# IO_Board.net
KiCad netlist of a schematic drawn in Altium Designer
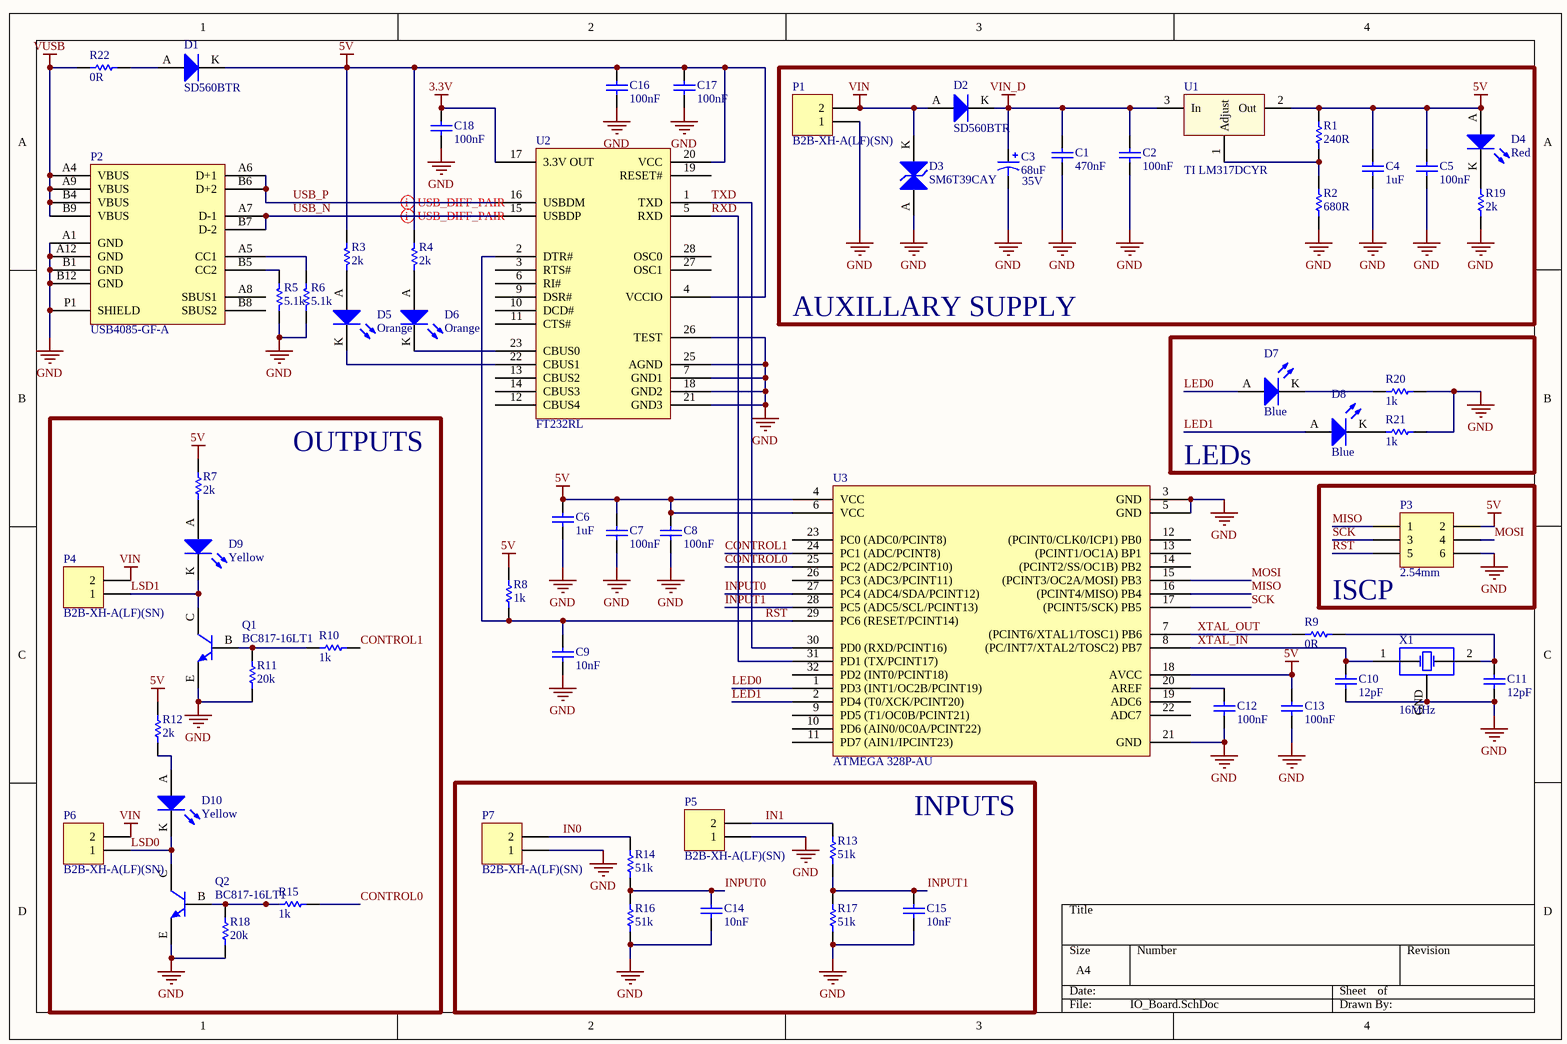
[diagram p0: IO_Board.SchDoc]

(export (version "E")
  (design (tool "Eeschema 10.0.6"))
  (components
    (comp (ref "C1")
      (value "470nF")
      (footprint "0805")
      (fields
        (field (name "PART NUMBER") "GCM21BR71H474KA37L")
        (field (name "TOLERANCE") "10%")
        (field (name "MANUFACTURER") "muRata")
      )
      (libsource (lib "ts_20-standard-library") (part "Capacitor"))
    )
    (comp (ref "C2")
      (value "100nF")
      (footprint "0805")
      (fields
        (field (name "PART NUMBER") "GCM21BR71E104KA37L")
        (field (name "TOLERANCE") "10%")
        (field (name "MANUFACTURER") "muRata")
      )
      (libsource (lib "ts_20-standard-library") (part "Capacitor"))
    )
    (comp (ref "C3")
      (value "68uF")
      (footprint "2924")
      (fields
        (field (name "PART NUMBER") "TAJV686K035RNJ")
        (field (name "TOLERANCE") "10%")
        (field (name "RATED VOLTAGE") "35V")
        (field (name "MANUFACTURER") "AVX Corporation")
      )
      (libsource (lib "ts_20-standard-library") (part "Capacitor (Polarised)"))
    )
    (comp (ref "C4")
      (value "1uF")
      (footprint "0805")
      (fields
        (field (name "PART NUMBER") "AC0805KKX7R8BB105")
        (field (name "TOLERANCE") "10%")
        (field (name "MANUFACTURER") "YAGEO")
      )
      (libsource (lib "ts_20-standard-library") (part "Capacitor"))
    )
    (comp (ref "C5")
      (value "100nF")
      (footprint "0805")
      (fields
        (field (name "PART NUMBER") "GCM21BR71E104KA37L")
        (field (name "TOLERANCE") "10%")
        (field (name "MANUFACTURER") "muRata")
      )
      (libsource (lib "ts_20-standard-library") (part "Capacitor"))
    )
    (comp (ref "C6")
      (value "1uF")
      (footprint "0805")
      (fields
        (field (name "PART NUMBER") "AC0805KKX7R8BB105")
        (field (name "TOLERANCE") "10%")
        (field (name "MANUFACTURER") "YAGEO")
      )
      (libsource (lib "ts_20-standard-library") (part "Capacitor"))
    )
    (comp (ref "C7")
      (value "100nF")
      (footprint "0805")
      (fields
        (field (name "PART NUMBER") "GCM21BR71E104KA37L")
        (field (name "TOLERANCE") "10%")
        (field (name "MANUFACTURER") "muRata")
      )
      (libsource (lib "ts_20-standard-library") (part "Capacitor"))
    )
    (comp (ref "C8")
      (value "100nF")
      (footprint "0805")
      (fields
        (field (name "PART NUMBER") "GCM21BR71E104KA37L")
        (field (name "TOLERANCE") "10%")
        (field (name "MANUFACTURER") "muRata")
      )
      (libsource (lib "ts_20-standard-library") (part "Capacitor"))
    )
    (comp (ref "C9")
      (value "10nF")
      (footprint "0805")
      (fields
        (field (name "PART NUMBER") "GCM2195C1H103JA16D")
        (field (name "TOLERANCE") "±5%")
        (field (name "MANUFACTURER") "muRata")
      )
      (libsource (lib "ts_20-standard-library") (part "Capacitor"))
    )
    (comp (ref "C10")
      (value "12pF")
      (footprint "0805")
      (fields
        (field (name "PART NUMBER") "GCM21B5c1H120JA37L")
        (field (name "TOLERANCE") "5%")
        (field (name "MANUFACTURER") "muRata")
      )
      (libsource (lib "ts_20-standard-library") (part "Capacitor"))
    )
    (comp (ref "C11")
      (value "12pF")
      (footprint "0805")
      (fields
        (field (name "PART NUMBER") "GCM21B5c1H120JA37L")
        (field (name "TOLERANCE") "5%")
        (field (name "MANUFACTURER") "muRata")
      )
      (libsource (lib "ts_20-standard-library") (part "Capacitor"))
    )
    (comp (ref "C12")
      (value "100nF")
      (footprint "0805")
      (fields
        (field (name "PART NUMBER") "GCM21BR71E104KA37L")
        (field (name "TOLERANCE") "10%")
        (field (name "MANUFACTURER") "muRata")
      )
      (libsource (lib "ts_20-standard-library") (part "Capacitor"))
    )
    (comp (ref "C13")
      (value "100nF")
      (footprint "0805")
      (fields
        (field (name "PART NUMBER") "GCM21BR71E104KA37L")
        (field (name "TOLERANCE") "10%")
        (field (name "MANUFACTURER") "muRata")
      )
      (libsource (lib "ts_20-standard-library") (part "Capacitor"))
    )
    (comp (ref "C14")
      (value "10nF")
      (footprint "0805")
      (fields
        (field (name "PART NUMBER") "GCM21BR71H103KA37L")
        (field (name "TOLERANCE") "10%")
        (field (name "MANUFACTURER") "muRata")
      )
      (libsource (lib "ts_20-standard-library") (part "Capacitor"))
    )
    (comp (ref "C15")
      (value "10nF")
      (footprint "0805")
      (fields
        (field (name "PART NUMBER") "GCM21BR71H103KA37L")
        (field (name "TOLERANCE") "10%")
        (field (name "MANUFACTURER") "muRata")
      )
      (libsource (lib "ts_20-standard-library") (part "Capacitor"))
    )
    (comp (ref "C16")
      (value "100nF")
      (footprint "0805")
      (fields
        (field (name "PART NUMBER") "GCM21BR71E104KA37L")
        (field (name "TOLERANCE") "10%")
        (field (name "MANUFACTURER") "muRata")
      )
      (libsource (lib "ts_20-standard-library") (part "Capacitor"))
    )
    (comp (ref "C17")
      (value "100nF")
      (footprint "0805")
      (fields
        (field (name "PART NUMBER") "GCM21BR71E104KA37L")
        (field (name "TOLERANCE") "10%")
        (field (name "MANUFACTURER") "muRata")
      )
      (libsource (lib "ts_20-standard-library") (part "Capacitor"))
    )
    (comp (ref "C18")
      (value "100nF")
      (footprint "0805")
      (fields
        (field (name "PART NUMBER") "GCM21BR71E104KA37L")
        (field (name "TOLERANCE") "10%")
        (field (name "MANUFACTURER") "muRata")
      )
      (libsource (lib "ts_20-standard-library") (part "Capacitor"))
    )
    (comp (ref "D1")
      (value "SD560BTR")
      (footprint "SMB Diode")
      (description "1.2V_F 600V 5A SMB")
      (fields
        (field (name "MANUFACTURER") "SMC Diode Solutions")
        (field (name "DIGIKEY PART NUMBER") "1655-1530-2-ND")
      )
      (libsource (lib "ts_20-standard-library") (part "Diode"))
    )
    (comp (ref "D2")
      (value "SD560BTR")
      (footprint "SMB Diode")
      (description "1.2V_F 600V 5A SMB")
      (fields
        (field (name "MANUFACTURER") "SMC Diode Solutions")
        (field (name "DIGIKEY PART NUMBER") "1655-1530-2-ND")
      )
      (libsource (lib "ts_20-standard-library") (part "Diode"))
    )
    (comp (ref "D3")
      (value "SM6T39CAY")
      (footprint "ST SMB Diode")
      (description "42.8V Clamp 93A (8/20µs) Ipp Tvs Diode Surface Mount SMB (DO-214AA)")
      (fields (field (name "MANUFACTURER") "ST"))
      (libsource (lib "ts_20-standard-library") (part "Bidirectional Zener Diode"))
    )
    (comp (ref "D4")
      (value "Red")
      (footprint "0805 LED")
      (description "Red LED Indication - Discrete 1.75V 0805 (2012 Metric)")
      (fields (field (name "PART NUMBER") "SML-210LTT86") (field (name "MANUFACTURER") "ROHM Semiconductor"))
      (libsource (lib "ts_20-standard-library") (part "LED"))
    )
    (comp (ref "D5")
      (value "Orange")
      (footprint "0805 LED")
      (description "Orange LED Indication - Discrete 1.75V 0805 (2012 Metric)")
      (fields (field (name "PART NUMBER") "SML-211DTT86") (field (name "MANUFACTURER") "ROHM Semiconductor"))
      (libsource (lib "ts_20-standard-library") (part "LED"))
    )
    (comp (ref "D6")
      (value "Orange")
      (footprint "0805 LED")
      (description "Orange LED Indication - Discrete 1.75V 0805 (2012 Metric)")
      (fields (field (name "PART NUMBER") "SML-211DTT86") (field (name "MANUFACTURER") "ROHM Semiconductor"))
      (libsource (lib "ts_20-standard-library") (part "LED"))
    )
    (comp (ref "D7")
      (value "Blue")
      (footprint "0805 LED")
      (description "LED BLUE CLEAR 2012 SMD")
      (fields
        (field (name "PART NUMBER") "SML-MN2BCTT86C")
        (field (name "MANUFACTURER") "ROHM Semiconductor")
      )
      (libsource (lib "ts_20-standard-library") (part "LED"))
    )
    (comp (ref "D8")
      (value "Blue")
      (footprint "0805 LED")
      (description "LED BLUE CLEAR 2012 SMD")
      (fields
        (field (name "PART NUMBER") "SML-MN2BCTT86C")
        (field (name "MANUFACTURER") "ROHM Semiconductor")
      )
      (libsource (lib "ts_20-standard-library") (part "LED"))
    )
    (comp (ref "D9")
      (value "Yellow")
      (footprint "0805 LED")
      (description "Yellow LED Indication - Discrete 1.75V 0805 (2012 Metric)")
      (fields (field (name "PART NUMBER") "SML-211YTT86") (field (name "MANUFACTURER") "ROHM Semiconductor"))
      (libsource (lib "ts_20-standard-library") (part "LED"))
    )
    (comp (ref "D10")
      (value "Yellow")
      (footprint "0805 LED")
      (description "Yellow LED Indication - Discrete 1.75V 0805 (2012 Metric)")
      (fields (field (name "PART NUMBER") "SML-211YTT86") (field (name "MANUFACTURER") "ROHM Semiconductor"))
      (libsource (lib "ts_20-standard-library") (part "LED"))
    )
    (comp (ref "P1")
      (value "B2B-XH-A(LF)(SN)")
      (footprint "XH 2 PIN VERT")
      (fields (field (name "DIGIKEY PART NUMBER") "455-2247-ND") (field (name "CONTACT") "Tin"))
      (libsource (lib "ts_20-standard-connectors") (part "Header 1x2"))
    )
    (comp (ref "P2")
      (value "USB4085-GF-A")
      (footprint "USB4085-GF-A")
      (description "USB - C (Type - C) USB 2.0 Receptacle Connector 16 Position Through Hole, Right Angle")
      (fields (field (name "DIGIKEY PART NUMBER") "2073-USB4085-GF-ACT-ND"))
      (libsource (lib "ts_20-standard-connectors") (part "USB4085-GF-A"))
    )
    (comp (ref "P3")
      (value "2.54mm")
      (footprint "TH 2.54mm Header 2x3")
      (fields (field (name "PART NUMBER") "TH 2.54mm Header 2x3") (field (name "CONTACT") "NA"))
      (libsource (lib "ts_20-standard-connectors") (part "Header 2x3"))
    )
    (comp (ref "P4")
      (value "B2B-XH-A(LF)(SN)")
      (footprint "XH 2 PIN VERT")
      (fields (field (name "DIGIKEY PART NUMBER") "455-2247-ND") (field (name "CONTACT") "Tin"))
      (libsource (lib "ts_20-standard-connectors") (part "Header 1x2"))
    )
    (comp (ref "P5")
      (value "B2B-XH-A(LF)(SN)")
      (footprint "XH 2 PIN VERT")
      (fields (field (name "DIGIKEY PART NUMBER") "455-2247-ND") (field (name "CONTACT") "Tin"))
      (libsource (lib "ts_20-standard-connectors") (part "Header 1x2"))
    )
    (comp (ref "P6")
      (value "B2B-XH-A(LF)(SN)")
      (footprint "XH 2 PIN VERT")
      (fields (field (name "DIGIKEY PART NUMBER") "455-2247-ND") (field (name "CONTACT") "Tin"))
      (libsource (lib "ts_20-standard-connectors") (part "Header 1x2"))
    )
    (comp (ref "P7")
      (value "B2B-XH-A(LF)(SN)")
      (footprint "XH 2 PIN VERT")
      (fields (field (name "DIGIKEY PART NUMBER") "455-2247-ND") (field (name "CONTACT") "Tin"))
      (libsource (lib "ts_20-standard-connectors") (part "Header 1x2"))
    )
    (comp (ref "Q1")
      (value "BC817-16LT1")
      (footprint "ON SOT-23 BJT")
      (description "300mW  BJT NPN Transistor")
      (fields
        (field (name "MANUFACTURER") "ON Semiconductor")
        (field (name "DIGIKEY PART NUMBER") "BC817-16LT1OSTR-ND")
      )
      (libsource (lib "ts_20-standard-library") (part "NPN"))
    )
    (comp (ref "Q2")
      (value "BC817-16LT1")
      (footprint "ON SOT-23 BJT")
      (description "300mW  BJT NPN Transistor")
      (fields
        (field (name "MANUFACTURER") "ON Semiconductor")
        (field (name "DIGIKEY PART NUMBER") "BC817-16LT1OSTR-ND")
      )
      (libsource (lib "ts_20-standard-library") (part "NPN"))
    )
    (comp (ref "R1")
      (value "240R")
      (footprint "0805")
      (fields
        (field (name "PART NUMBER") "RC0805FR07240RL")
        (field (name "MANUFACTURER") "YAGEO")
        (field (name "TOLERANCE") "0.01")
      )
      (libsource (lib "ts_20-standard-library") (part "Resistor"))
    )
    (comp (ref "R2")
      (value "680R")
      (footprint "0805")
      (fields
        (field (name "PART NUMBER") "RC0805FR07680RL")
        (field (name "MANUFACTURER") "YAGEO")
        (field (name "TOLERANCE") "0.01")
      )
      (libsource (lib "ts_20-standard-library") (part "Resistor"))
    )
    (comp (ref "R3")
      (value "2k")
      (footprint "0805")
      (fields
        (field (name "PART NUMBER") "RC0805FR072KL")
        (field (name "MANUFACTURER") "YAGEO")
        (field (name "TOLERANCE") "0.01")
      )
      (libsource (lib "ts_20-standard-library") (part "Resistor"))
    )
    (comp (ref "R4")
      (value "2k")
      (footprint "0805")
      (fields
        (field (name "PART NUMBER") "RC0805FR072KL")
        (field (name "MANUFACTURER") "YAGEO")
        (field (name "TOLERANCE") "0.01")
      )
      (libsource (lib "ts_20-standard-library") (part "Resistor"))
    )
    (comp (ref "R5")
      (value "5.1k")
      (footprint "0805")
      (fields
        (field (name "PART NUMBER") "RC0805FR075K1L")
        (field (name "MANUFACTURER") "YAGEO")
        (field (name "TOLERANCE") "0.01")
      )
      (libsource (lib "ts_20-standard-library") (part "Resistor"))
    )
    (comp (ref "R6")
      (value "5.1k")
      (footprint "0805")
      (fields
        (field (name "PART NUMBER") "RC0805FR075K1L")
        (field (name "MANUFACTURER") "YAGEO")
        (field (name "TOLERANCE") "0.01")
      )
      (libsource (lib "ts_20-standard-library") (part "Resistor"))
    )
    (comp (ref "R7")
      (value "2k")
      (footprint "0805")
      (fields
        (field (name "PART NUMBER") "RC0805FR072KL")
        (field (name "MANUFACTURER") "YAGEO")
        (field (name "TOLERANCE") "0.01")
      )
      (libsource (lib "ts_20-standard-library") (part "Resistor"))
    )
    (comp (ref "R8")
      (value "1k")
      (footprint "0805")
      (fields
        (field (name "PART NUMBER") "RC0805FR071KL")
        (field (name "MANUFACTURER") "YAGEO")
        (field (name "TOLERANCE") "0.01")
      )
      (libsource (lib "ts_20-standard-library") (part "Resistor"))
    )
    (comp (ref "R9")
      (value "0R")
      (footprint "0805")
      (fields
        (field (name "PART NUMBER") "RC0805FR070RL")
        (field (name "MANUFACTURER") "YAGEO")
        (field (name "TOLERANCE") "0.01")
      )
      (libsource (lib "ts_20-standard-library") (part "Resistor"))
    )
    (comp (ref "R10")
      (value "1k")
      (footprint "0805")
      (fields
        (field (name "PART NUMBER") "RC0805FR071KL")
        (field (name "MANUFACTURER") "YAGEO")
        (field (name "TOLERANCE") "0.01")
      )
      (libsource (lib "ts_20-standard-library") (part "Resistor"))
    )
    (comp (ref "R11")
      (value "20k")
      (footprint "0805")
      (fields
        (field (name "PART NUMBER") "RC0805FR0720KL")
        (field (name "MANUFACTURER") "YAGEO")
        (field (name "TOLERANCE") "0.01")
      )
      (libsource (lib "ts_20-standard-library") (part "Resistor"))
    )
    (comp (ref "R12")
      (value "2k")
      (footprint "0805")
      (fields
        (field (name "PART NUMBER") "RC0805FR072KL")
        (field (name "MANUFACTURER") "YAGEO")
        (field (name "TOLERANCE") "0.01")
      )
      (libsource (lib "ts_20-standard-library") (part "Resistor"))
    )
    (comp (ref "R13")
      (value "51k")
      (footprint "0805")
      (fields
        (field (name "PART NUMBER") "RC0805FR0751KL")
        (field (name "MANUFACTURER") "YAGEO")
        (field (name "TOLERANCE") "0.01")
      )
      (libsource (lib "ts_20-standard-library") (part "Resistor"))
    )
    (comp (ref "R14")
      (value "51k")
      (footprint "0805")
      (fields
        (field (name "PART NUMBER") "RC0805FR0751KL")
        (field (name "MANUFACTURER") "YAGEO")
        (field (name "TOLERANCE") "0.01")
      )
      (libsource (lib "ts_20-standard-library") (part "Resistor"))
    )
    (comp (ref "R15")
      (value "1k")
      (footprint "0805")
      (fields
        (field (name "PART NUMBER") "RC0805FR071KL")
        (field (name "MANUFACTURER") "YAGEO")
        (field (name "TOLERANCE") "0.01")
      )
      (libsource (lib "ts_20-standard-library") (part "Resistor"))
    )
    (comp (ref "R16")
      (value "51k")
      (footprint "0805")
      (fields
        (field (name "PART NUMBER") "RC0805FR0751KL")
        (field (name "MANUFACTURER") "YAGEO")
        (field (name "TOLERANCE") "0.01")
      )
      (libsource (lib "ts_20-standard-library") (part "Resistor"))
    )
    (comp (ref "R17")
      (value "51k")
      (footprint "0805")
      (fields
        (field (name "PART NUMBER") "RC0805FR0751KL")
        (field (name "MANUFACTURER") "YAGEO")
        (field (name "TOLERANCE") "0.01")
      )
      (libsource (lib "ts_20-standard-library") (part "Resistor"))
    )
    (comp (ref "R18")
      (value "20k")
      (footprint "0805")
      (fields
        (field (name "PART NUMBER") "RC0805FR0720KL")
        (field (name "MANUFACTURER") "YAGEO")
        (field (name "TOLERANCE") "0.01")
      )
      (libsource (lib "ts_20-standard-library") (part "Resistor"))
    )
    (comp (ref "R19")
      (value "2k")
      (footprint "0805")
      (fields
        (field (name "PART NUMBER") "RC0805FR072KL")
        (field (name "MANUFACTURER") "YAGEO")
        (field (name "TOLERANCE") "0.01")
      )
      (libsource (lib "ts_20-standard-library") (part "Resistor"))
    )
    (comp (ref "R20")
      (value "1k")
      (footprint "0805")
      (fields
        (field (name "PART NUMBER") "RC0805FR071KL")
        (field (name "MANUFACTURER") "YAGEO")
        (field (name "TOLERANCE") "0.01")
      )
      (libsource (lib "ts_20-standard-library") (part "Resistor"))
    )
    (comp (ref "R21")
      (value "1k")
      (footprint "0805")
      (fields
        (field (name "PART NUMBER") "RC0805FR071KL")
        (field (name "MANUFACTURER") "YAGEO")
        (field (name "TOLERANCE") "0.01")
      )
      (libsource (lib "ts_20-standard-library") (part "Resistor"))
    )
    (comp (ref "R22")
      (value "0R")
      (footprint "0805")
      (fields
        (field (name "PART NUMBER") "RC0805FR070RL")
        (field (name "MANUFACTURER") "YAGEO")
        (field (name "TOLERANCE") "0.01")
      )
      (libsource (lib "ts_20-standard-library") (part "Resistor"))
    )
    (comp (ref "U1")
      (value "TI LM317DCYR")
      (footprint "TI SOT-223")
      (description "Linear Voltage Regulator IC 1 Output 1.5A SOT-223-4")
      (fields
        (field (name "MANUFACTURER") "Texas Instruments")
        (field (name "DIGIKEY PART NUMBER") "296-12602-1-ND")
      )
      (libsource (lib "ts_20-standard-library") (part "TI LM317"))
    )
    (comp (ref "U2")
      (value "FT232RL")
      (footprint "FTDI 28-SSOP")
      (description "USB Bridge, USB to UART USB 2.0 UART Interface 28-SSOP")
      (fields (field (name "MANUFACTURER") "FTDI") (field (name "DIGIKEY PART NUMBER") "768-1007-1-ND"))
      (libsource (lib "ts_20-standard-library") (part "FT232RL"))
    )
    (comp (ref "U3")
      (value "ATMEGA 328P-AU")
      (footprint "ATMEL TQFP-32")
      (description "AVR AVR® ATmega Microcontroller IC 8-Bit 20MHz 32KB (16K x 16) FLASH 32-TQFP (7x7)")
      (fields (field (name "MANUFACTURER") "ATMEL") (field (name "DIGIKEY PART NUMBER") "ATMEGA328P-AU-ND"))
      (libsource (lib "ts_20-standard-library") (part "ATMEGA 328P-AU"))
    )
    (comp (ref "X1")
      (value "16MHz")
      (footprint "Abracon 4-SMD 3.2x2.5")
      (fields
        (field (name "PART NUMBER") "ABM8AIG-16.000MHZ-12-2Z-T3")
        (field (name "MANUFACTURER") "Abracon LLC")
        (field (name "DIGIKEY PART NUMBER") "535-13386-1-ND")
      )
      (libsource (lib "ts_20-standard-library") (part "Crystal (Shielded)"))
    )
  )
  (nets
    (net (code "1") (name "/CONTROL0") (class "Default")
      (node (ref "R15") (pin "2") (pinfunction "2_2") (pintype "passive"))
      (node (ref "U3") (pin "25") (pinfunction "PC2_(ADC2/PCINT10)_25") (pintype "passive"))
    )
    (net (code "2") (name "/CONTROL1") (class "Default")
      (node (ref "R10") (pin "2") (pinfunction "2_2") (pintype "passive"))
      (node (ref "U3") (pin "24") (pinfunction "PC1_(ADC/PCINT8)_24") (pintype "passive"))
    )
    (net (code "3") (name "/IN0") (class "Default")
      (node (ref "P7") (pin "2") (pinfunction "2_2") (pintype "passive"))
      (node (ref "R14") (pin "1") (pinfunction "1_1") (pintype "passive"))
    )
    (net (code "4") (name "/IN1") (class "Default")
      (node (ref "P5") (pin "2") (pinfunction "2_2") (pintype "passive"))
      (node (ref "R13") (pin "1") (pinfunction "1_1") (pintype "passive"))
    )
    (net (code "5") (name "/INPUT0") (class "Default")
      (node (ref "C14") (pin "2") (pinfunction "2_2") (pintype "passive"))
      (node (ref "R14") (pin "2") (pinfunction "2_2") (pintype "passive"))
      (node (ref "R16") (pin "1") (pinfunction "1_1") (pintype "passive"))
      (node (ref "U3") (pin "27") (pinfunction "PC4_(ADC4/SDA/PCINT12)_27") (pintype "passive"))
    )
    (net (code "6") (name "/INPUT1") (class "Default")
      (node (ref "C15") (pin "2") (pinfunction "2_2") (pintype "passive"))
      (node (ref "R13") (pin "2") (pinfunction "2_2") (pintype "passive"))
      (node (ref "R17") (pin "1") (pinfunction "1_1") (pintype "passive"))
      (node (ref "U3") (pin "28") (pinfunction "PC5_(ADC5/SCL/PCINT13)_28") (pintype "passive"))
    )
    (net (code "7") (name "/LED0") (class "Default")
      (node (ref "D7") (pin "A") (pinfunction "A_A") (pintype "passive"))
      (node (ref "U3") (pin "1") (pinfunction "PD3_(INT1/OC2B/PCINT19)_1") (pintype "passive"))
    )
    (net (code "8") (name "/LED1") (class "Default")
      (node (ref "D8") (pin "A") (pinfunction "A_A") (pintype "passive"))
      (node (ref "U3") (pin "2") (pinfunction "PD4_(T0/XCK/PCINT20)_2") (pintype "passive"))
    )
    (net (code "9") (name "/LSD0") (class "Default")
      (node (ref "D10") (pin "K") (pinfunction "K_K") (pintype "passive"))
      (node (ref "P6") (pin "1") (pinfunction "1_1") (pintype "passive"))
      (node (ref "Q2") (pin "C") (pinfunction "C_C") (pintype "passive"))
    )
    (net (code "10") (name "/LSD1") (class "Default")
      (node (ref "D9") (pin "K") (pinfunction "K_K") (pintype "passive"))
      (node (ref "P4") (pin "1") (pinfunction "1_1") (pintype "passive"))
      (node (ref "Q1") (pin "C") (pinfunction "C_C") (pintype "passive"))
    )
    (net (code "11") (name "/MISO") (class "Default")
      (node (ref "P3") (pin "1") (pinfunction "1_1") (pintype "passive"))
      (node (ref "U3") (pin "16") (pinfunction "(PCINT4/MISO)_PB4_16") (pintype "passive"))
    )
    (net (code "12") (name "/MOSI") (class "Default")
      (node (ref "P3") (pin "4") (pinfunction "4_4") (pintype "passive"))
      (node (ref "U3") (pin "15") (pinfunction "(PCINT3/OC2A/MOSI)_PB3_15") (pintype "passive"))
    )
    (net (code "13") (name "/RST") (class "Default")
      (node (ref "C9") (pin "2") (pinfunction "2_2") (pintype "passive"))
      (node (ref "P3") (pin "5") (pinfunction "5_5") (pintype "passive"))
      (node (ref "R8") (pin "1") (pinfunction "1_1") (pintype "passive"))
      (node (ref "U2") (pin "2") (pinfunction "DTR#_2") (pintype "power_in"))
      (node (ref "U3") (pin "29") (pinfunction "PC6_(RESET/PCINT14)_29") (pintype "passive"))
    )
    (net (code "14") (name "/RXD") (class "Default")
      (node (ref "U2") (pin "5") (pinfunction "RXD_5") (pintype "power_in"))
      (node (ref "U3") (pin "31") (pinfunction "PD1_(TX/PCINT17)_31") (pintype "passive"))
    )
    (net (code "15") (name "/SCK") (class "Default")
      (node (ref "P3") (pin "3") (pinfunction "3_3") (pintype "passive"))
      (node (ref "U3") (pin "17") (pinfunction "(PCINT5/SCK)_PB5_17") (pintype "passive"))
    )
    (net (code "16") (name "/TXD") (class "Default")
      (node (ref "U2") (pin "1") (pinfunction "TXD_1") (pintype "power_in"))
      (node (ref "U3") (pin "30") (pinfunction "PD0_(RXD/PCINT16)_30") (pintype "passive"))
    )
    (net (code "17") (name "/USB_N") (class "Default")
      (node (ref "P2") (pin "A7") (pinfunction "D-1_A7") (pintype "passive"))
      (node (ref "P2") (pin "B7") (pinfunction "D-2_B7") (pintype "passive"))
      (node (ref "U2") (pin "15") (pinfunction "USBDP_15") (pintype "power_in"))
    )
    (net (code "18") (name "/USB_P") (class "Default")
      (node (ref "P2") (pin "A6") (pinfunction "D+1_A6") (pintype "passive"))
      (node (ref "P2") (pin "B6") (pinfunction "D+2_B6") (pintype "passive"))
      (node (ref "U2") (pin "16") (pinfunction "USBDM_16") (pintype "power_in"))
    )
    (net (code "19") (name "/XTAL_IN") (class "Default")
      (node (ref "C10") (pin "2") (pinfunction "2_2") (pintype "passive"))
      (node (ref "U3") (pin "8") (pinfunction "(PC/INT7/XTAL2/TOSC2)_PB7_8") (pintype "passive"))
      (node (ref "X1") (pin "1") (pinfunction "OSC1_1") (pintype "passive"))
    )
    (net (code "20") (name "/XTAL_OUT") (class "Default")
      (node (ref "R9") (pin "1") (pinfunction "1_1") (pintype "passive"))
      (node (ref "U3") (pin "7") (pinfunction "(PCINT6/XTAL1/TOSC1)_PB6_7") (pintype "passive"))
    )
    (net (code "21") (name "3.3V") (class "Default")
      (node (ref "C18") (pin "2") (pinfunction "2_2") (pintype "passive"))
      (node (ref "U2") (pin "17") (pinfunction "3.3V_OUT_17") (pintype "power_in"))
    )
    (net (code "22") (name "5V") (class "Default")
      (node (ref "C13") (pin "2") (pinfunction "2_2") (pintype "passive"))
      (node (ref "C16") (pin "2") (pinfunction "2_2") (pintype "passive"))
      (node (ref "C17") (pin "2") (pinfunction "2_2") (pintype "passive"))
      (node (ref "C4") (pin "2") (pinfunction "2_2") (pintype "passive"))
      (node (ref "C5") (pin "2") (pinfunction "2_2") (pintype "passive"))
      (node (ref "C6") (pin "2") (pinfunction "2_2") (pintype "passive"))
      (node (ref "C7") (pin "2") (pinfunction "2_2") (pintype "passive"))
      (node (ref "C8") (pin "2") (pinfunction "2_2") (pintype "passive"))
      (node (ref "D1") (pin "K") (pinfunction "K_K") (pintype "passive"))
      (node (ref "D4") (pin "A") (pinfunction "A_A") (pintype "passive"))
      (node (ref "P3") (pin "2") (pinfunction "2_2") (pintype "passive"))
      (node (ref "R1") (pin "2") (pinfunction "2_2") (pintype "passive"))
      (node (ref "R12") (pin "2") (pinfunction "2_2") (pintype "passive"))
      (node (ref "R3") (pin "2") (pinfunction "2_2") (pintype "passive"))
      (node (ref "R4") (pin "2") (pinfunction "2_2") (pintype "passive"))
      (node (ref "R7") (pin "2") (pinfunction "2_2") (pintype "passive"))
      (node (ref "R8") (pin "2") (pinfunction "2_2") (pintype "passive"))
      (node (ref "U1") (pin "2") (pinfunction "Out_2") (pintype "passive"))
      (node (ref "U2") (pin "20") (pinfunction "VCC_20") (pintype "power_in"))
      (node (ref "U2") (pin "4") (pinfunction "VCCIO_4") (pintype "power_in"))
      (node (ref "U3") (pin "18") (pinfunction "AVCC_18") (pintype "passive"))
      (node (ref "U3") (pin "4") (pinfunction "VCC_4") (pintype "passive"))
      (node (ref "U3") (pin "6") (pinfunction "VCC_6") (pintype "passive"))
    )
    (net (code "23") (name "GND") (class "Default")
      (node (ref "C1") (pin "1") (pinfunction "1_1") (pintype "passive"))
      (node (ref "C10") (pin "1") (pinfunction "1_1") (pintype "passive"))
      (node (ref "C11") (pin "1") (pinfunction "1_1") (pintype "passive"))
      (node (ref "C12") (pin "1") (pinfunction "1_1") (pintype "passive"))
      (node (ref "C13") (pin "1") (pinfunction "1_1") (pintype "passive"))
      (node (ref "C14") (pin "1") (pinfunction "1_1") (pintype "passive"))
      (node (ref "C15") (pin "1") (pinfunction "1_1") (pintype "passive"))
      (node (ref "C16") (pin "1") (pinfunction "1_1") (pintype "passive"))
      (node (ref "C17") (pin "1") (pinfunction "1_1") (pintype "passive"))
      (node (ref "C18") (pin "1") (pinfunction "1_1") (pintype "passive"))
      (node (ref "C2") (pin "1") (pinfunction "1_1") (pintype "passive"))
      (node (ref "C3") (pin "1") (pinfunction "1_1") (pintype "passive"))
      (node (ref "C4") (pin "1") (pinfunction "1_1") (pintype "passive"))
      (node (ref "C5") (pin "1") (pinfunction "1_1") (pintype "passive"))
      (node (ref "C6") (pin "1") (pinfunction "1_1") (pintype "passive"))
      (node (ref "C7") (pin "1") (pinfunction "1_1") (pintype "passive"))
      (node (ref "C8") (pin "1") (pinfunction "1_1") (pintype "passive"))
      (node (ref "C9") (pin "1") (pinfunction "1_1") (pintype "passive"))
      (node (ref "D3") (pin "A") (pinfunction "A_A") (pintype "passive"))
      (node (ref "P1") (pin "1") (pinfunction "1_1") (pintype "passive"))
      (node (ref "P2") (pin "A1") (pinfunction "GND_A1") (pintype "passive"))
      (node (ref "P2") (pin "A12") (pinfunction "GND_A12") (pintype "passive"))
      (node (ref "P2") (pin "B1") (pinfunction "GND_B1") (pintype "passive"))
      (node (ref "P2") (pin "B12") (pinfunction "GND_B12") (pintype "passive"))
      (node (ref "P2") (pin "P1") (pinfunction "SHIELD_P1") (pintype "passive"))
      (node (ref "P3") (pin "6") (pinfunction "6_6") (pintype "passive"))
      (node (ref "P5") (pin "1") (pinfunction "1_1") (pintype "passive"))
      (node (ref "P7") (pin "1") (pinfunction "1_1") (pintype "passive"))
      (node (ref "Q1") (pin "E") (pinfunction "E_E") (pintype "passive"))
      (node (ref "Q2") (pin "E") (pinfunction "E_E") (pintype "passive"))
      (node (ref "R11") (pin "1") (pinfunction "1_1") (pintype "passive"))
      (node (ref "R16") (pin "2") (pinfunction "2_2") (pintype "passive"))
      (node (ref "R17") (pin "2") (pinfunction "2_2") (pintype "passive"))
      (node (ref "R18") (pin "1") (pinfunction "1_1") (pintype "passive"))
      (node (ref "R19") (pin "1") (pinfunction "1_1") (pintype "passive"))
      (node (ref "R2") (pin "1") (pinfunction "1_1") (pintype "passive"))
      (node (ref "R20") (pin "1") (pinfunction "1_1") (pintype "passive"))
      (node (ref "R21") (pin "1") (pinfunction "1_1") (pintype "passive"))
      (node (ref "R5") (pin "1") (pinfunction "1_1") (pintype "passive"))
      (node (ref "R6") (pin "1") (pinfunction "1_1") (pintype "passive"))
      (node (ref "U2") (pin "18") (pinfunction "GND2_18") (pintype "power_in"))
      (node (ref "U2") (pin "21") (pinfunction "GND3_21") (pintype "power_in"))
      (node (ref "U2") (pin "25") (pinfunction "AGND_25") (pintype "power_in"))
      (node (ref "U2") (pin "26") (pinfunction "TEST_26") (pintype "power_in"))
      (node (ref "U2") (pin "7") (pinfunction "GND1_7") (pintype "power_in"))
      (node (ref "U3") (pin "21") (pinfunction "GND_21") (pintype "passive"))
      (node (ref "U3") (pin "3") (pinfunction "GND_3") (pintype "passive"))
      (node (ref "U3") (pin "5") (pinfunction "GND_5") (pintype "passive"))
      (node (ref "X1") (pin "GND") (pinfunction "GND_GND") (pintype "passive"))
    )
    (net (code "24") (name "Net-(D1-PadA)") (class "Default")
      (node (ref "D1") (pin "A") (pinfunction "A_A") (pintype "passive"))
      (node (ref "R22") (pin "2") (pinfunction "2_2") (pintype "passive"))
    )
    (net (code "25") (name "Net-(D4-PadK)") (class "Default")
      (node (ref "D4") (pin "K") (pinfunction "K_K") (pintype "passive"))
      (node (ref "R19") (pin "2") (pinfunction "2_2") (pintype "passive"))
    )
    (net (code "26") (name "Net-(D5-PadA)") (class "Default")
      (node (ref "D5") (pin "A") (pinfunction "A_A") (pintype "passive"))
      (node (ref "R3") (pin "1") (pinfunction "1_1") (pintype "passive"))
    )
    (net (code "27") (name "Net-(D6-PadA)") (class "Default")
      (node (ref "D6") (pin "A") (pinfunction "A_A") (pintype "passive"))
      (node (ref "R4") (pin "1") (pinfunction "1_1") (pintype "passive"))
    )
    (net (code "28") (name "Net-(D7-PadK)") (class "Default")
      (node (ref "D7") (pin "K") (pinfunction "K_K") (pintype "passive"))
      (node (ref "R20") (pin "2") (pinfunction "2_2") (pintype "passive"))
    )
    (net (code "29") (name "Net-(D8-PadK)") (class "Default")
      (node (ref "D8") (pin "K") (pinfunction "K_K") (pintype "passive"))
      (node (ref "R21") (pin "2") (pinfunction "2_2") (pintype "passive"))
    )
    (net (code "30") (name "Net-(D9-PadA)") (class "Default")
      (node (ref "D9") (pin "A") (pinfunction "A_A") (pintype "passive"))
      (node (ref "R7") (pin "1") (pinfunction "1_1") (pintype "passive"))
    )
    (net (code "31") (name "Net-(D10-PadA)") (class "Default")
      (node (ref "D10") (pin "A") (pinfunction "A_A") (pintype "passive"))
      (node (ref "R12") (pin "1") (pinfunction "1_1") (pintype "passive"))
    )
    (net (code "32") (name "Net-(P2-CC1)") (class "Default")
      (node (ref "P2") (pin "A5") (pinfunction "CC1_A5") (pintype "passive"))
      (node (ref "R6") (pin "2") (pinfunction "2_2") (pintype "passive"))
    )
    (net (code "33") (name "Net-(P2-CC2)") (class "Default")
      (node (ref "P2") (pin "B5") (pinfunction "CC2_B5") (pintype "passive"))
      (node (ref "R5") (pin "2") (pinfunction "2_2") (pintype "passive"))
    )
    (net (code "34") (name "Net-(Q1-PadB)") (class "Default")
      (node (ref "Q1") (pin "B") (pinfunction "B_B") (pintype "passive"))
      (node (ref "R10") (pin "1") (pinfunction "1_1") (pintype "passive"))
      (node (ref "R11") (pin "2") (pinfunction "2_2") (pintype "passive"))
    )
    (net (code "35") (name "Net-(Q2-PadB)") (class "Default")
      (node (ref "Q2") (pin "B") (pinfunction "B_B") (pintype "passive"))
      (node (ref "R15") (pin "1") (pinfunction "1_1") (pintype "passive"))
      (node (ref "R18") (pin "2") (pinfunction "2_2") (pintype "passive"))
    )
    (net (code "36") (name "Net-(U1-Adjust)") (class "Default")
      (node (ref "R1") (pin "1") (pinfunction "1_1") (pintype "passive"))
      (node (ref "R2") (pin "2") (pinfunction "2_2") (pintype "passive"))
      (node (ref "U1") (pin "1") (pinfunction "Adjust_1") (pintype "passive"))
    )
    (net (code "37") (name "Net-(U2-CBUS0)") (class "Default")
      (node (ref "D6") (pin "K") (pinfunction "K_K") (pintype "passive"))
      (node (ref "U2") (pin "23") (pinfunction "CBUS0_23") (pintype "power_in"))
    )
    (net (code "38") (name "Net-(U2-CBUS1)") (class "Default")
      (node (ref "D5") (pin "K") (pinfunction "K_K") (pintype "passive"))
      (node (ref "U2") (pin "22") (pinfunction "CBUS1_22") (pintype "power_in"))
    )
    (net (code "39") (name "Net-(U3-AREF)") (class "Default")
      (node (ref "C12") (pin "2") (pinfunction "2_2") (pintype "passive"))
      (node (ref "U3") (pin "20") (pinfunction "AREF_20") (pintype "passive"))
    )
    (net (code "40") (name "Net-(X1-OSC2)") (class "Default")
      (node (ref "C11") (pin "2") (pinfunction "2_2") (pintype "passive"))
      (node (ref "R9") (pin "2") (pinfunction "2_2") (pintype "passive"))
      (node (ref "X1") (pin "2") (pinfunction "OSC2_2") (pintype "passive"))
    )
    (net (code "41") (name "VIN") (class "Default")
      (node (ref "D2") (pin "A") (pinfunction "A_A") (pintype "passive"))
      (node (ref "D3") (pin "K") (pinfunction "K_K") (pintype "passive"))
      (node (ref "P1") (pin "2") (pinfunction "2_2") (pintype "passive"))
      (node (ref "P4") (pin "2") (pinfunction "2_2") (pintype "passive"))
      (node (ref "P6") (pin "2") (pinfunction "2_2") (pintype "passive"))
    )
    (net (code "42") (name "VIN_D") (class "Default")
      (node (ref "C1") (pin "2") (pinfunction "2_2") (pintype "passive"))
      (node (ref "C2") (pin "2") (pinfunction "2_2") (pintype "passive"))
      (node (ref "C3") (pin "2") (pinfunction "2_2") (pintype "passive"))
      (node (ref "D2") (pin "K") (pinfunction "K_K") (pintype "passive"))
      (node (ref "U1") (pin "3") (pinfunction "In_3") (pintype "passive"))
    )
    (net (code "43") (name "VUSB") (class "Default")
      (node (ref "P2") (pin "A4") (pinfunction "VBUS_A4") (pintype "passive"))
      (node (ref "P2") (pin "A9") (pinfunction "VBUS_A9") (pintype "passive"))
      (node (ref "P2") (pin "B4") (pinfunction "VBUS_B4") (pintype "passive"))
      (node (ref "P2") (pin "B9") (pinfunction "VBUS_B9") (pintype "passive"))
      (node (ref "R22") (pin "1") (pinfunction "1_1") (pintype "passive"))
    )
    (net (code "44") (name "unconnected-(P2-SBUS1-PadA8)") (class "Default")
      (node (ref "P2") (pin "A8") (pinfunction "SBUS1_A8") (pintype "passive"))
    )
    (net (code "45") (name "unconnected-(P2-SBUS2-PadB8)") (class "Default")
      (node (ref "P2") (pin "B8") (pinfunction "SBUS2_B8") (pintype "passive"))
    )
    (net (code "46") (name "unconnected-(U2-CBUS2-Pad13)") (class "Default")
      (node (ref "U2") (pin "13") (pinfunction "CBUS2_13") (pintype "power_in"))
    )
    (net (code "47") (name "unconnected-(U2-CBUS3-Pad14)") (class "Default")
      (node (ref "U2") (pin "14") (pinfunction "CBUS3_14") (pintype "power_in"))
    )
    (net (code "48") (name "unconnected-(U2-CBUS4-Pad12)") (class "Default")
      (node (ref "U2") (pin "12") (pinfunction "CBUS4_12") (pintype "power_in"))
    )
    (net (code "49") (name "unconnected-(U2-CTS#-Pad11)") (class "Default")
      (node (ref "U2") (pin "11") (pinfunction "CTS#_11") (pintype "power_in"))
    )
    (net (code "50") (name "unconnected-(U2-DCD#-Pad10)") (class "Default")
      (node (ref "U2") (pin "10") (pinfunction "DCD#_10") (pintype "power_in"))
    )
    (net (code "51") (name "unconnected-(U2-DSR#-Pad9)") (class "Default")
      (node (ref "U2") (pin "9") (pinfunction "DSR#_9") (pintype "power_in"))
    )
    (net (code "52") (name "unconnected-(U2-OSC0-Pad28)") (class "Default")
      (node (ref "U2") (pin "28") (pinfunction "OSC0_28") (pintype "power_in"))
    )
    (net (code "53") (name "unconnected-(U2-OSC1-Pad27)") (class "Default")
      (node (ref "U2") (pin "27") (pinfunction "OSC1_27") (pintype "power_in"))
    )
    (net (code "54") (name "unconnected-(U2-RESET#-Pad19)") (class "Default")
      (node (ref "U2") (pin "19") (pinfunction "RESET#_19") (pintype "power_in"))
    )
    (net (code "55") (name "unconnected-(U2-RI#-Pad6)") (class "Default")
      (node (ref "U2") (pin "6") (pinfunction "RI#_6") (pintype "power_in"))
    )
    (net (code "56") (name "unconnected-(U2-RTS#-Pad3)") (class "Default")
      (node (ref "U2") (pin "3") (pinfunction "RTS#_3") (pintype "power_in"))
    )
    (net (code "57") (name "unconnected-(U3-(PCINT0{slash}CLK0{slash}ICP1)_PB0-Pad12)") (class "Default")
      (node (ref "U3") (pin "12") (pinfunction "(PCINT0/CLK0/ICP1)_PB0_12") (pintype "passive"))
    )
    (net (code "58") (name "unconnected-(U3-(PCINT1{slash}OC1A)_BP1-Pad13)") (class "Default")
      (node (ref "U3") (pin "13") (pinfunction "(PCINT1/OC1A)_BP1_13") (pintype "passive"))
    )
    (net (code "59") (name "unconnected-(U3-(PCINT2{slash}SS{slash}OC1B)_PB2-Pad14)") (class "Default")
      (node (ref "U3") (pin "14") (pinfunction "(PCINT2/SS/OC1B)_PB2_14") (pintype "passive"))
    )
    (net (code "60") (name "unconnected-(U3-ADC6-Pad19)") (class "Default")
      (node (ref "U3") (pin "19") (pinfunction "ADC6_19") (pintype "passive"))
    )
    (net (code "61") (name "unconnected-(U3-ADC7-Pad22)") (class "Default")
      (node (ref "U3") (pin "22") (pinfunction "ADC7_22") (pintype "passive"))
    )
    (net (code "62") (name "unconnected-(U3-PC0_(ADC0{slash}PCINT8)-Pad23)") (class "Default")
      (node (ref "U3") (pin "23") (pinfunction "PC0_(ADC0/PCINT8)_23") (pintype "passive"))
    )
    (net (code "63") (name "unconnected-(U3-PC3_(ADC3{slash}PCINT11)-Pad26)") (class "Default")
      (node (ref "U3") (pin "26") (pinfunction "PC3_(ADC3/PCINT11)_26") (pintype "passive"))
    )
    (net (code "64") (name "unconnected-(U3-PD2_(INT0{slash}PCINT18)-Pad32)") (class "Default")
      (node (ref "U3") (pin "32") (pinfunction "PD2_(INT0/PCINT18)_32") (pintype "passive"))
    )
    (net (code "65") (name "unconnected-(U3-PD5_(T1{slash}OC0B{slash}PCINT21)-Pad9)") (class "Default")
      (node (ref "U3") (pin "9") (pinfunction "PD5_(T1/OC0B/PCINT21)_9") (pintype "passive"))
    )
    (net (code "66") (name "unconnected-(U3-PD6_(AIN0{slash}0C0A{slash}PCINT22)-Pad10)") (class "Default")
      (node (ref "U3") (pin "10") (pinfunction "PD6_(AIN0/0C0A/PCINT22)_10") (pintype "passive"))
    )
    (net (code "67") (name "unconnected-(U3-PD7_(AIN1{slash}IPCINT23)-Pad11)") (class "Default")
      (node (ref "U3") (pin "11") (pinfunction "PD7_(AIN1/IPCINT23)_11") (pintype "passive"))
    )
  )
)
